# Shifter_SMD_v16.net
KiCad netlist of a schematic drawn in EAGLE
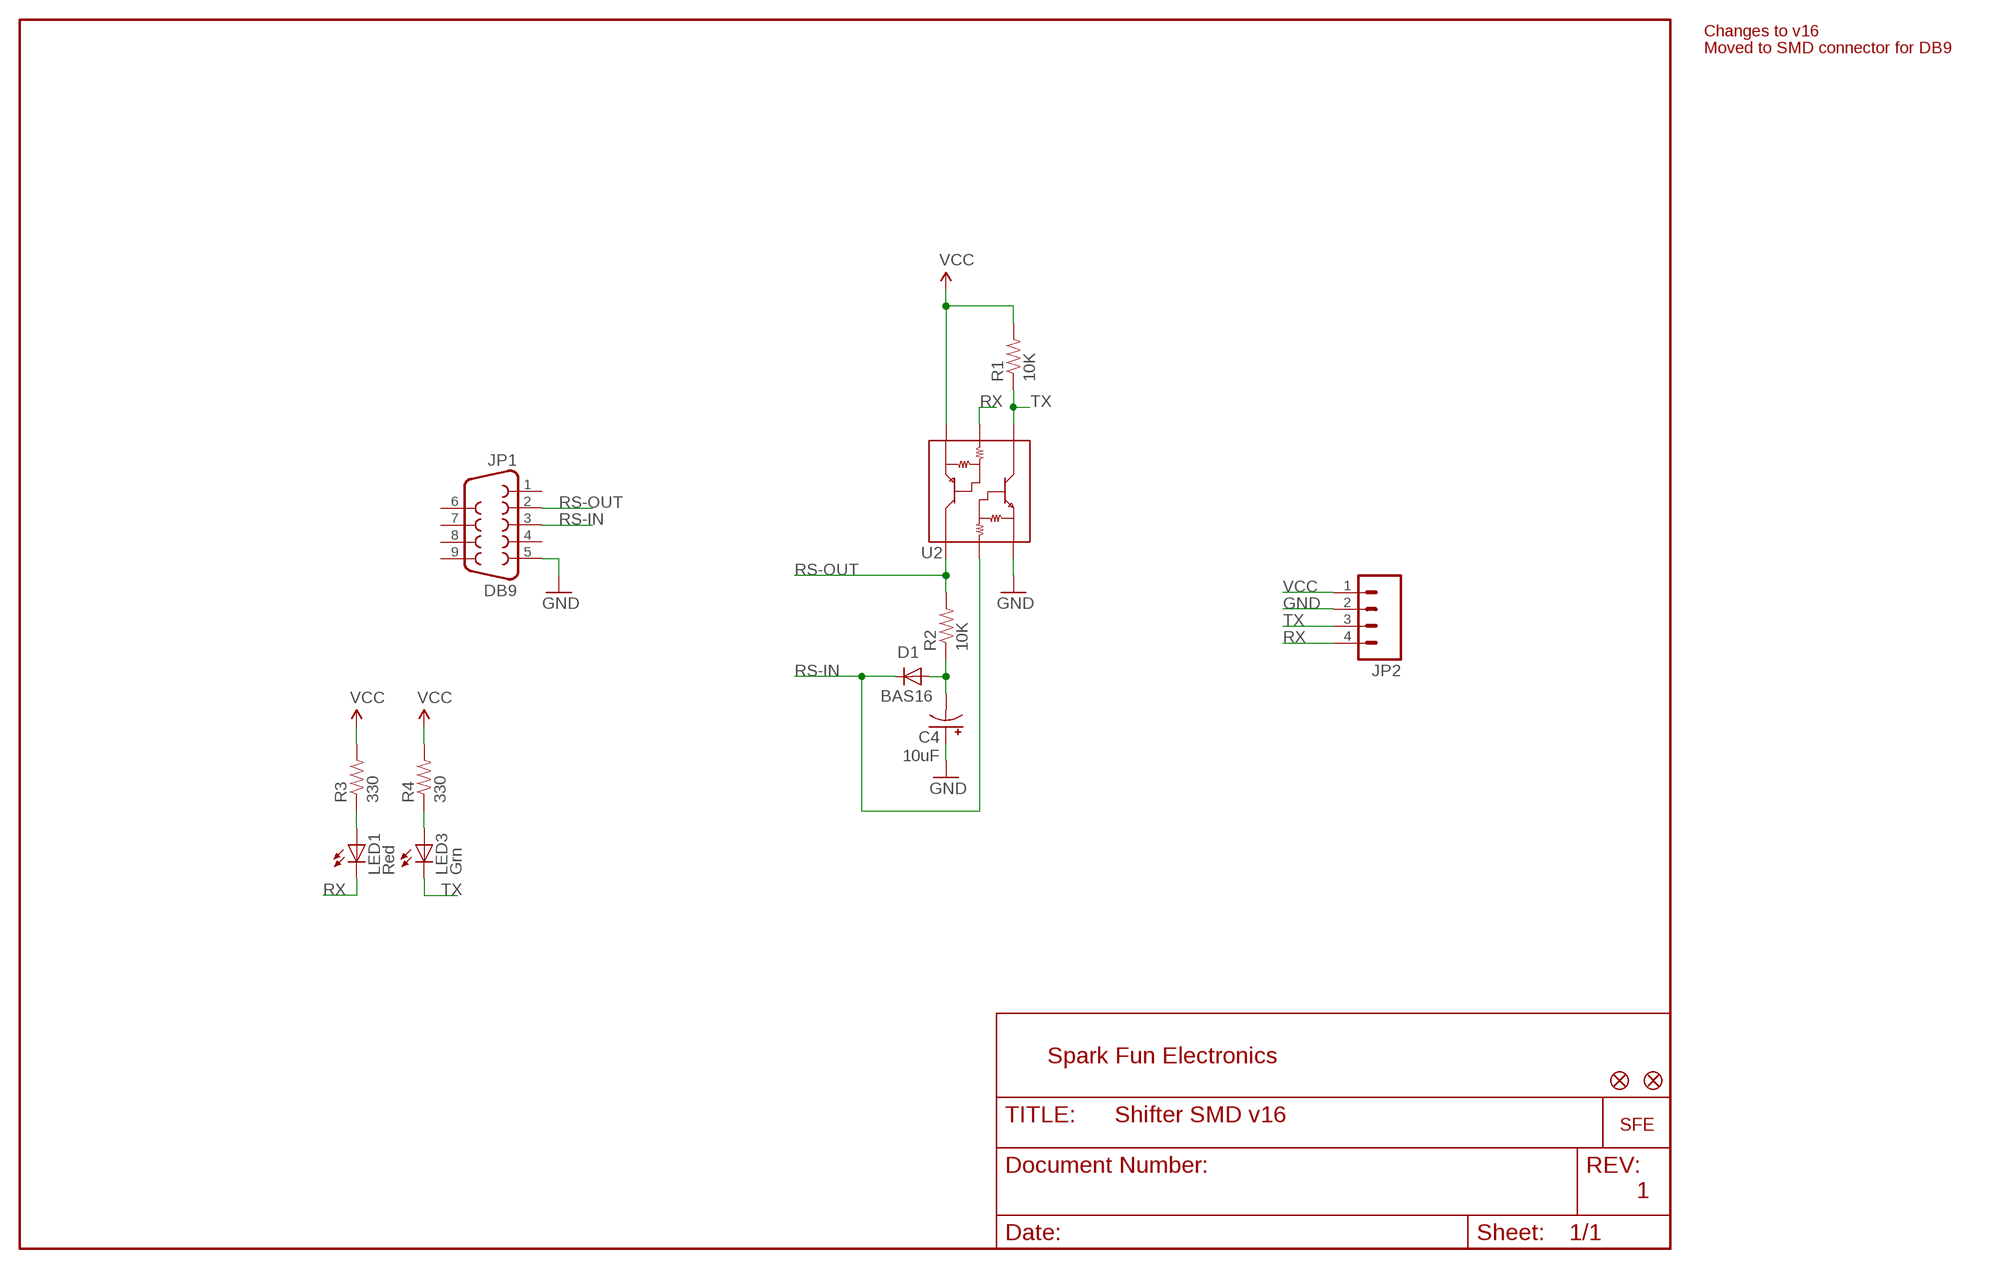
[diagram p0: schematic, sheet 1]

(export (version "E")
  (design (tool "Eeschema 10.0.6"))
  (components
    (comp (ref "C4")
      (value "10uF")
      (footprint "eagle-import:EIA3216")
      (libsource (lib "eagle-import") (part "CAP_POL1206"))
    )
    (comp (ref "D1")
      (value "BAS16")
      (footprint "eagle-import:SOD-323")
      (libsource (lib "eagle-import") (part "DIODESOD"))
    )
    (comp (ref "E$1")
      (value "FIDUCIAL1X2")
      (footprint "eagle-import:FIDUCIAL-1X2")
      (libsource (lib "eagle-import") (part "FIDUCIAL1X2"))
    )
    (comp (ref "E$2")
      (value "FIDUCIAL1X2")
      (footprint "eagle-import:FIDUCIAL-1X2")
      (libsource (lib "eagle-import") (part "FIDUCIAL1X2"))
    )
    (comp (ref "JP1")
      (value "DB9")
      (footprint "eagle-import:DB9-L17SM209S114T")
      (libsource (lib "eagle-import") (part "DB9L17SM209S114T"))
    )
    (comp (ref "JP2")
      (value "M04PTH")
      (footprint "eagle-import:1X04")
      (libsource (lib "eagle-import") (part "M04PTH"))
    )
    (comp (ref "LED1")
      (value "Red")
      (footprint "eagle-import:LED-1206")
      (libsource (lib "eagle-import") (part "LED1206"))
    )
    (comp (ref "LED3")
      (value "Grn")
      (footprint "eagle-import:LED-1206")
      (libsource (lib "eagle-import") (part "LED1206"))
    )
    (comp (ref "R1")
      (value "10K")
      (footprint "eagle-import:0603-RES")
      (libsource (lib "eagle-import") (part "RESISTOR0603-RES"))
    )
    (comp (ref "R2")
      (value "10K")
      (footprint "eagle-import:0603-RES")
      (libsource (lib "eagle-import") (part "RESISTOR0603-RES"))
    )
    (comp (ref "R3")
      (value "330")
      (footprint "eagle-import:0603-RES")
      (libsource (lib "eagle-import") (part "RESISTOR0603-RES"))
    )
    (comp (ref "R4")
      (value "330")
      (footprint "eagle-import:0603-RES")
      (libsource (lib "eagle-import") (part "RESISTOR0603-RES"))
    )
    (comp (ref "U$1")
      (value "LOGO-SFENEW")
      (footprint "eagle-import:SFE-NEW-WEBLOGO")
      (libsource (lib "eagle-import") (part "LOGO-SFENEW"))
    )
    (comp (ref "U2")
      (value "XN04312")
      (footprint "eagle-import:SOT23-6")
      (libsource (lib "eagle-import") (part "XN04312SOT"))
    )
  )
  (nets
    (net (code "1") (name "/RS-IN") (class "Default")
      (node (ref "D1") (pin "1") (pinfunction "C_1") (pintype "passive"))
      (node (ref "JP1") (pin "3") (pinfunction "3_3") (pintype "passive"))
      (node (ref "U2") (pin "5") (pinfunction "B1_5") (pintype "bidirectional"))
    )
    (net (code "2") (name "/RS-OUT") (class "Default")
      (node (ref "JP1") (pin "2") (pinfunction "2_2") (pintype "passive"))
      (node (ref "R2") (pin "2") (pinfunction "2_2") (pintype "passive"))
      (node (ref "U2") (pin "4") (pinfunction "C2_4") (pintype "bidirectional"))
    )
    (net (code "3") (name "/RX") (class "Default")
      (node (ref "JP2") (pin "4") (pinfunction "4_4") (pintype "passive"))
      (node (ref "LED1") (pin "C") (pinfunction "C_C") (pintype "passive"))
      (node (ref "U2") (pin "2") (pinfunction "B2_2") (pintype "bidirectional"))
    )
    (net (code "4") (name "/TX") (class "Default")
      (node (ref "JP2") (pin "3") (pinfunction "3_3") (pintype "passive"))
      (node (ref "LED3") (pin "C") (pinfunction "C_C") (pintype "passive"))
      (node (ref "R1") (pin "1") (pinfunction "1_1") (pintype "passive"))
      (node (ref "U2") (pin "1") (pinfunction "C1_1") (pintype "bidirectional"))
    )
    (net (code "5") (name "GND") (class "Default")
      (node (ref "C4") (pin "A") (pinfunction "+_A") (pintype "passive"))
      (node (ref "JP1") (pin "5") (pinfunction "5_5") (pintype "passive"))
      (node (ref "JP2") (pin "2") (pinfunction "2_2") (pintype "passive"))
      (node (ref "U2") (pin "6") (pinfunction "E1_6") (pintype "bidirectional"))
    )
    (net (code "6") (name "Net-(C4--)") (class "Default")
      (node (ref "C4") (pin "C") (pinfunction "-_C") (pintype "passive"))
      (node (ref "D1") (pin "2") (pinfunction "A_2") (pintype "passive"))
      (node (ref "R2") (pin "1") (pinfunction "1_1") (pintype "passive"))
    )
    (net (code "7") (name "Net-(LED1-PadA)") (class "Default")
      (node (ref "LED1") (pin "A") (pinfunction "A_A") (pintype "passive"))
      (node (ref "R3") (pin "1") (pinfunction "1_1") (pintype "passive"))
    )
    (net (code "8") (name "Net-(LED3-PadA)") (class "Default")
      (node (ref "LED3") (pin "A") (pinfunction "A_A") (pintype "passive"))
      (node (ref "R4") (pin "1") (pinfunction "1_1") (pintype "passive"))
    )
    (net (code "9") (name "VCC") (class "Default")
      (node (ref "JP2") (pin "1") (pinfunction "1_1") (pintype "passive"))
      (node (ref "R1") (pin "2") (pinfunction "2_2") (pintype "passive"))
      (node (ref "R3") (pin "2") (pinfunction "2_2") (pintype "passive"))
      (node (ref "R4") (pin "2") (pinfunction "2_2") (pintype "passive"))
      (node (ref "U2") (pin "3") (pinfunction "E2_3") (pintype "bidirectional"))
    )
    (net (code "10") (name "unconnected-(JP1-Pad1)") (class "Default")
      (node (ref "JP1") (pin "1") (pinfunction "1_1") (pintype "passive"))
    )
    (net (code "11") (name "unconnected-(JP1-Pad4)") (class "Default")
      (node (ref "JP1") (pin "4") (pinfunction "4_4") (pintype "passive"))
    )
    (net (code "12") (name "unconnected-(JP1-Pad6)") (class "Default")
      (node (ref "JP1") (pin "6") (pinfunction "6_6") (pintype "passive"))
    )
    (net (code "13") (name "unconnected-(JP1-Pad7)") (class "Default")
      (node (ref "JP1") (pin "7") (pinfunction "7_7") (pintype "passive"))
    )
    (net (code "14") (name "unconnected-(JP1-Pad8)") (class "Default")
      (node (ref "JP1") (pin "8") (pinfunction "8_8") (pintype "passive"))
    )
    (net (code "15") (name "unconnected-(JP1-Pad9)") (class "Default")
      (node (ref "JP1") (pin "9") (pinfunction "9_9") (pintype "passive"))
    )
  )
)
